# xx_backplane_shield_xi.net
KiCad netlist of a schematic drawn in EAGLE
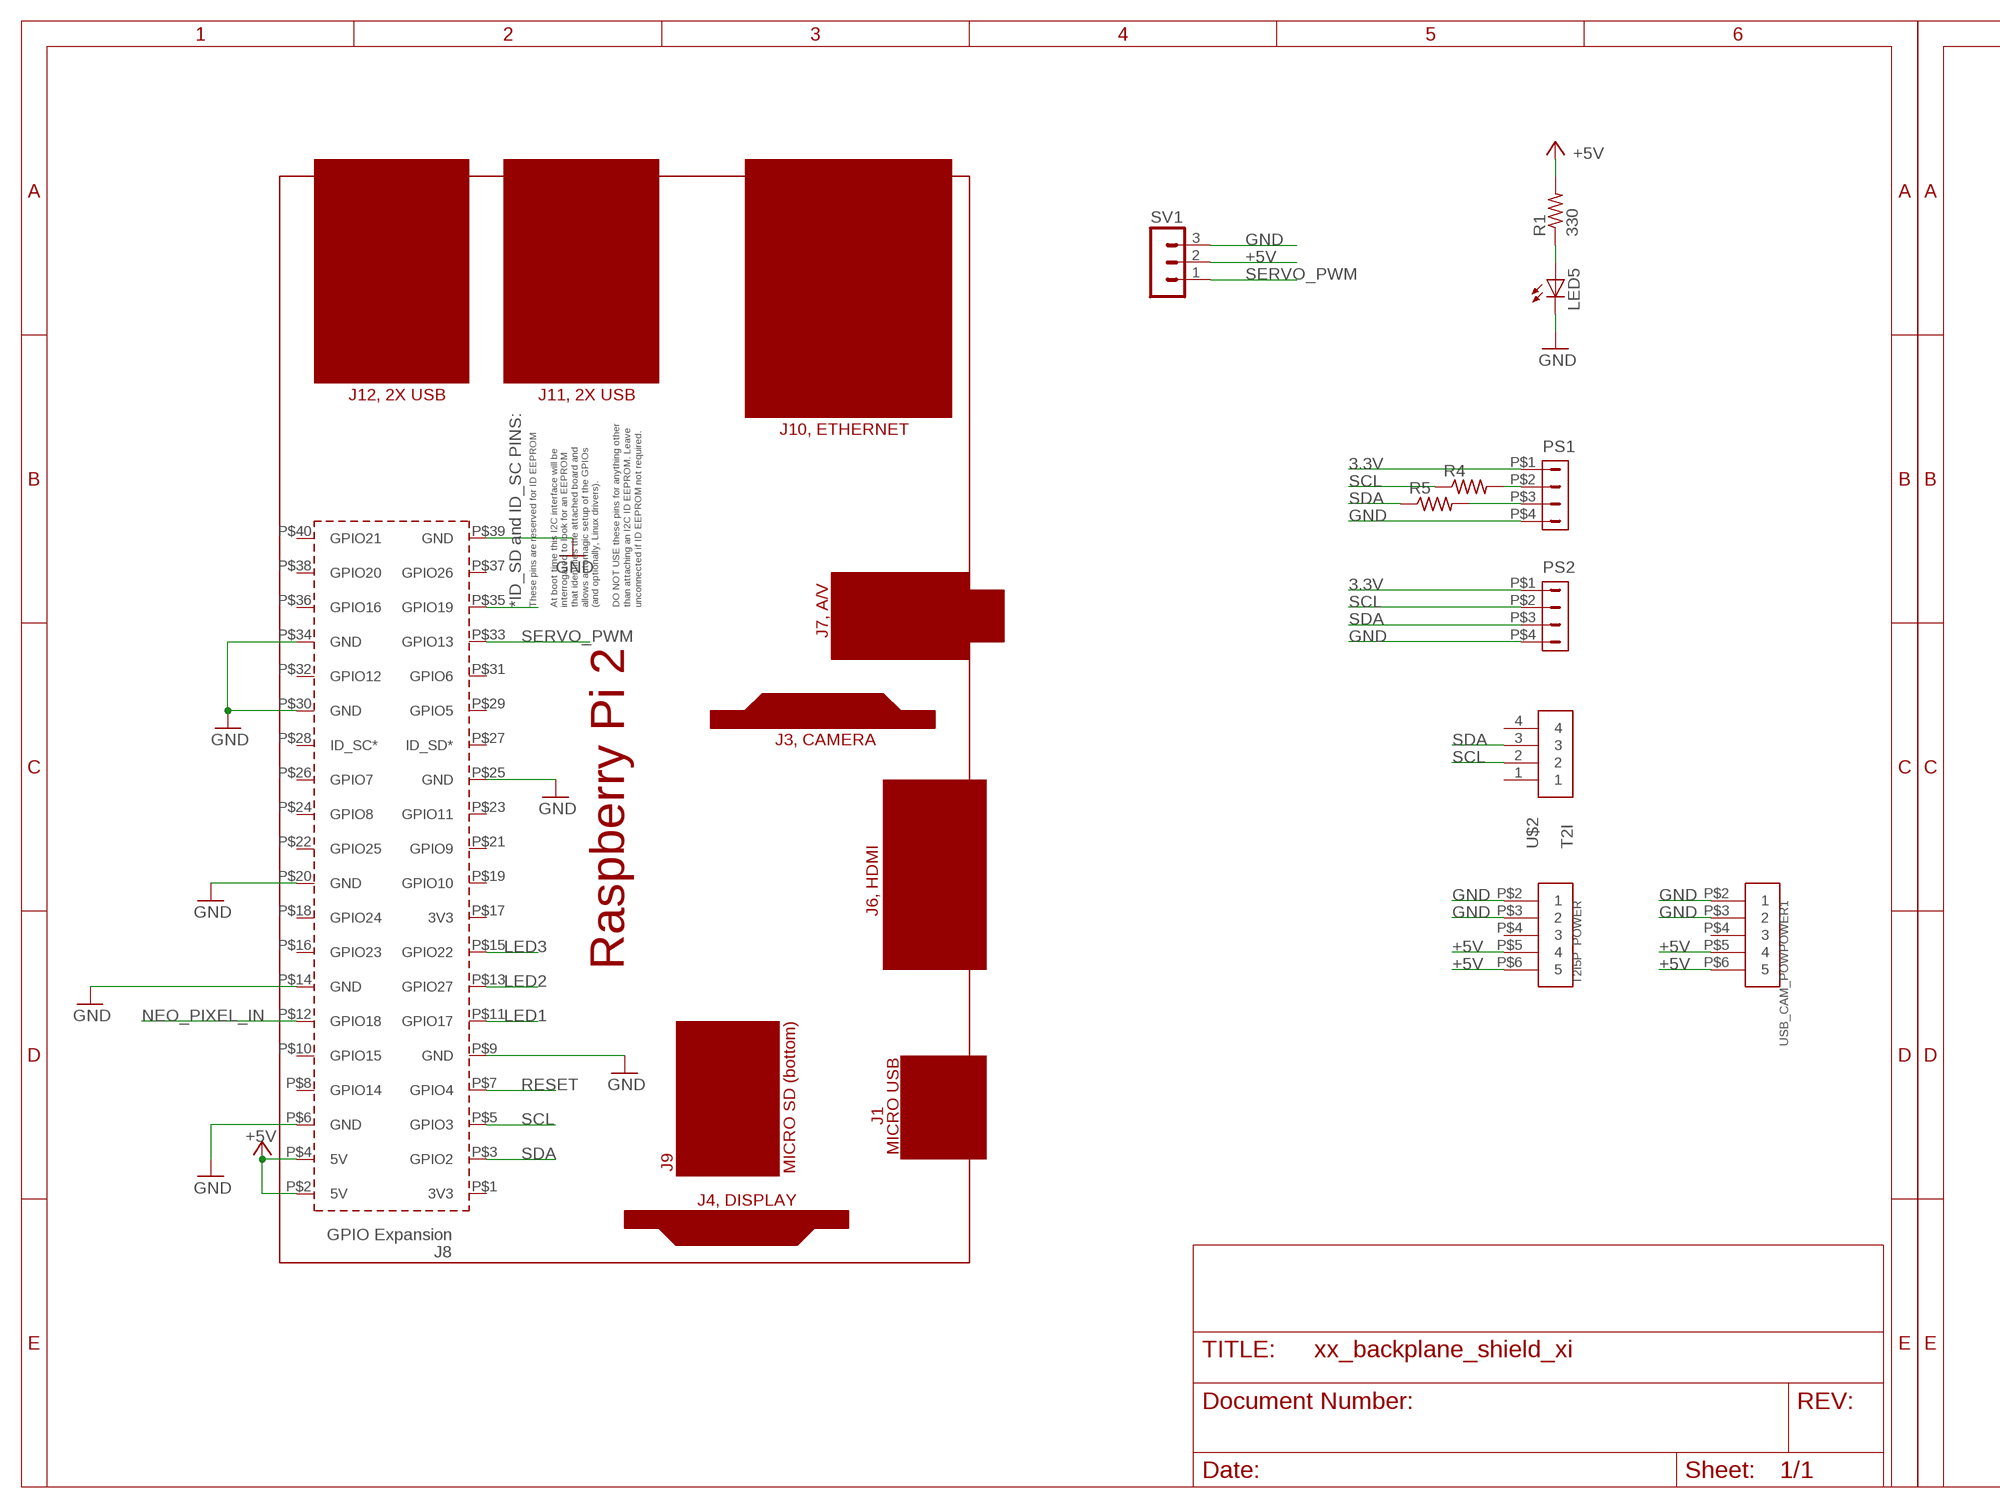
[diagram p0: schematic, sheet 1, part 1 of 2]
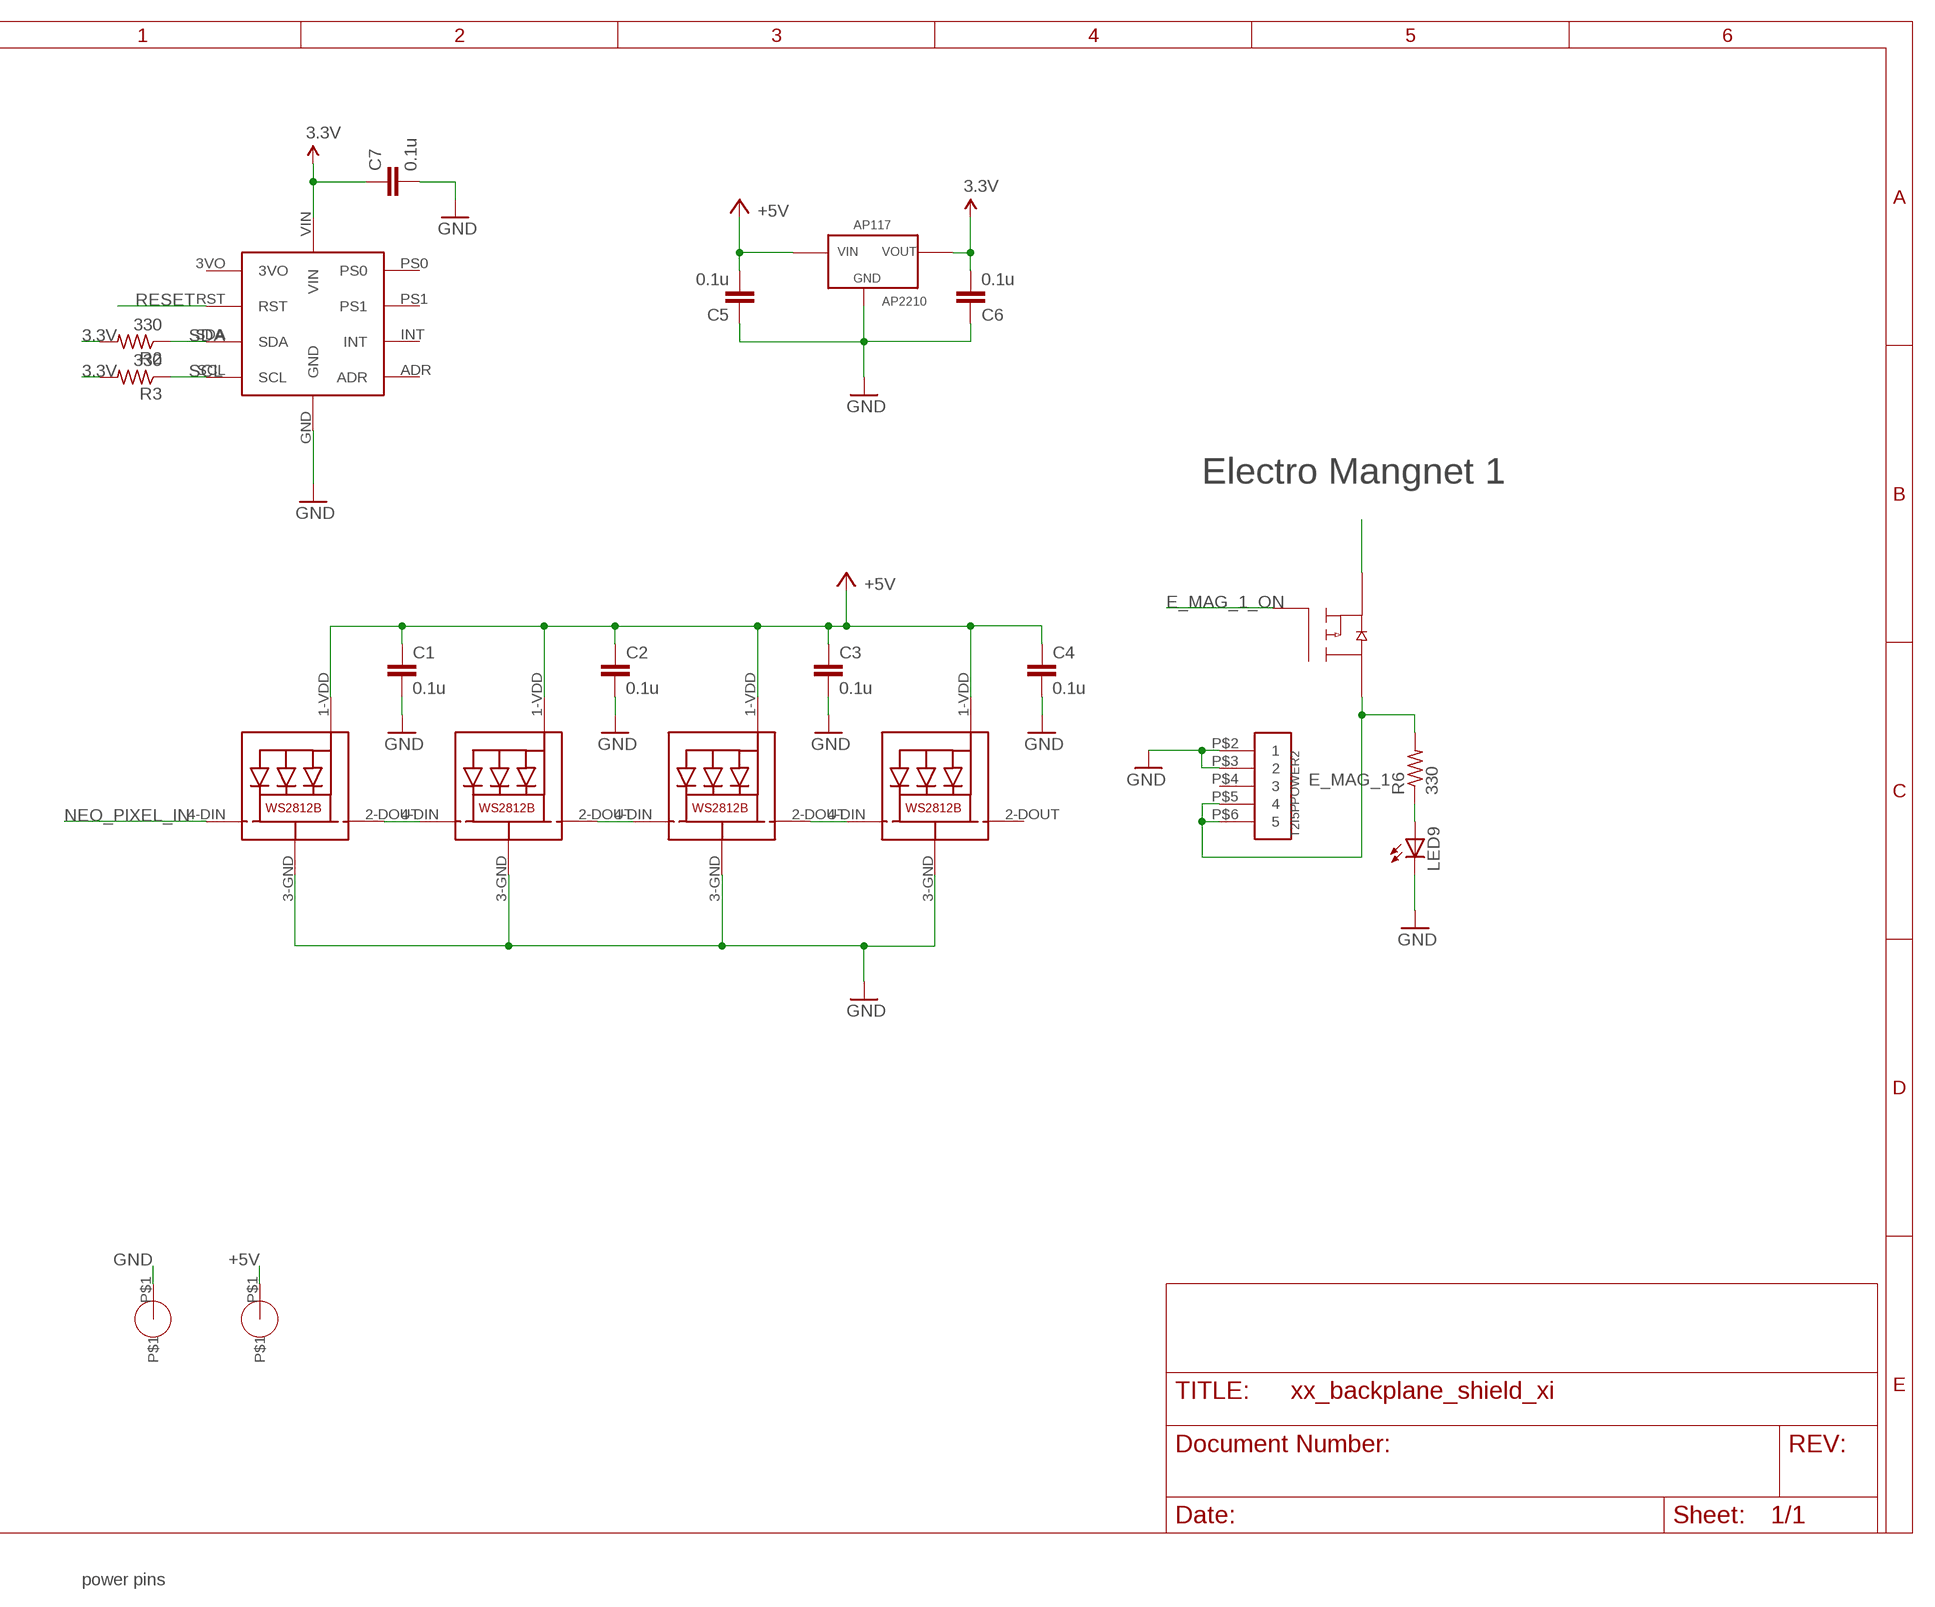
[diagram p1: schematic, sheet 1, part 2 of 2]

(export (version "E")
  (design (tool "Eeschema 10.0.6"))
  (components
    (comp (ref "C1")
      (value "0.1u")
      (footprint "eagle-import:0603-CAP")
      (libsource (lib "eagle-import") (part "CAP0603-CAP"))
    )
    (comp (ref "C2")
      (value "0.1u")
      (footprint "eagle-import:0603-CAP")
      (libsource (lib "eagle-import") (part "CAP0603-CAP"))
    )
    (comp (ref "C3")
      (value "0.1u")
      (footprint "eagle-import:0603-CAP")
      (libsource (lib "eagle-import") (part "CAP0603-CAP"))
    )
    (comp (ref "C4")
      (value "0.1u")
      (footprint "eagle-import:0603-CAP")
      (libsource (lib "eagle-import") (part "CAP0603-CAP"))
    )
    (comp (ref "C5")
      (value "0.1u")
      (footprint "eagle-import:0603-CAP")
      (libsource (lib "eagle-import") (part "CAP0603-CAP"))
    )
    (comp (ref "C6")
      (value "0.1u")
      (footprint "eagle-import:0603-CAP")
      (libsource (lib "eagle-import") (part "CAP0603-CAP"))
    )
    (comp (ref "C7")
      (value "0.1u")
      (footprint "eagle-import:0603-CAP")
      (libsource (lib "eagle-import") (part "CAP0603-CAP"))
    )
    (comp (ref "LED1")
      (value "WS2812B5050")
      (footprint "eagle-import:WS2812B")
      (libsource (lib "eagle-import") (part "WS2812B5050"))
    )
    (comp (ref "LED2")
      (value "WS2812B5050")
      (footprint "eagle-import:WS2812B")
      (libsource (lib "eagle-import") (part "WS2812B5050"))
    )
    (comp (ref "LED3")
      (value "WS2812B5050")
      (footprint "eagle-import:WS2812B")
      (libsource (lib "eagle-import") (part "WS2812B5050"))
    )
    (comp (ref "LED4")
      (value "WS2812B5050")
      (footprint "eagle-import:WS2812B")
      (libsource (lib "eagle-import") (part "WS2812B5050"))
    )
    (comp (ref "LED5")
      (value "LEDSML0603")
      (footprint "eagle-import:SML0603")
      (libsource (lib "eagle-import") (part "LEDSML0603"))
    )
    (comp (ref "LED9")
      (value "LEDSML0603")
      (footprint "eagle-import:SML0603")
      (libsource (lib "eagle-import") (part "LEDSML0603"))
    )
    (comp (ref "PCB1")
      (value "RPI2")
      (footprint "eagle-import:RPI2")
      (libsource (lib "eagle-import") (part "RPI2"))
    )
    (comp (ref "POWER")
      (value "T2I5P")
      (footprint "eagle-import:T2I5P")
      (libsource (lib "eagle-import") (part "T2I5P"))
    )
    (comp (ref "POWER1")
      (value "USB_CAM_POW")
      (footprint "eagle-import:T2I5P")
      (libsource (lib "eagle-import") (part "T2I5P"))
    )
    (comp (ref "POWER2")
      (value "T2I5P")
      (footprint "eagle-import:T2I5P")
      (libsource (lib "eagle-import") (part "T2I5P"))
    )
    (comp (ref "PS1")
      (value "DF13-4P-1.25DSA")
      (footprint "eagle-import:DF13-4P-1.25DSA")
      (libsource (lib "eagle-import") (part "DF13-4P-1.25DSA"))
    )
    (comp (ref "PS2")
      (value "DF13-4P-1.25DSA")
      (footprint "eagle-import:DF13-4P-1.25DSA")
      (libsource (lib "eagle-import") (part "DF13-4P-1.25DSA"))
    )
    (comp (ref "R1")
      (value "330")
      (footprint "eagle-import:R0603")
      (libsource (lib "eagle-import") (part "R-US_R0603"))
    )
    (comp (ref "R2")
      (value "330")
      (footprint "eagle-import:R0603")
      (libsource (lib "eagle-import") (part "R-US_R0603"))
    )
    (comp (ref "R3")
      (value "330")
      (footprint "eagle-import:R0603")
      (libsource (lib "eagle-import") (part "R-US_R0603"))
    )
    (comp (ref "R4")
      (value "0 Ohms")
      (footprint "eagle-import:R0603")
      (libsource (lib "eagle-import") (part "resistor_348_R-US_R0603"))
    )
    (comp (ref "R5")
      (value "0 ohms")
      (footprint "eagle-import:R0603")
      (libsource (lib "eagle-import") (part "resistor_348_R-US_R0603"))
    )
    (comp (ref "R6")
      (value "330")
      (footprint "eagle-import:R0603")
      (libsource (lib "eagle-import") (part "R-US_R0603"))
    )
    (comp (ref "SV1")
      (value "MA03-1")
      (footprint "eagle-import:MA03-1")
      (libsource (lib "eagle-import") (part "MA03-1"))
    )
    (comp (ref "U$2")
      (value "T2I")
      (footprint "eagle-import:T2I")
      (libsource (lib "eagle-import") (part "T2I"))
    )
    (comp (ref "U$3")
      (value "BNO055_9DOF_BREAKOUT")
      (footprint "eagle-import:BNO055")
      (libsource (lib "eagle-import") (part "BNO055_9DOF_BREAKOUT"))
    )
    (comp (ref "U$4")
      (value "THROUGHOLE")
      (footprint "eagle-import:THROUGHHOLE")
      (libsource (lib "eagle-import") (part "THROUGHOLE"))
    )
    (comp (ref "U$5")
      (value "AP2210")
      (footprint "eagle-import:SOT-23-3")
      (libsource (lib "eagle-import") (part "AP2210"))
    )
    (comp (ref "U$6")
      (value "THROUGHOLE")
      (footprint "eagle-import:THROUGHHOLE")
      (libsource (lib "eagle-import") (part "THROUGHOLE"))
    )
    (comp (ref "U1")
      (value "FQB27P06")
      (footprint "eagle-import:TO263-3")
      (libsource (lib "eagle-import") (part "FQB27P06"))
    )
  )
  (nets
    (net (code "1") (name "+5V") (class "Default")
      (node (ref "C1") (pin "1") (pinfunction "1_1") (pintype "passive"))
      (node (ref "C2") (pin "1") (pinfunction "1_1") (pintype "passive"))
      (node (ref "C3") (pin "1") (pinfunction "1_1") (pintype "passive"))
      (node (ref "C4") (pin "1") (pinfunction "1_1") (pintype "passive"))
      (node (ref "C5") (pin "2") (pinfunction "2_2") (pintype "passive"))
      (node (ref "LED1") (pin "1-VDD") (pinfunction "VDD_1-VDD") (pintype "power_in"))
      (node (ref "LED2") (pin "1-VDD") (pinfunction "VDD_1-VDD") (pintype "power_in"))
      (node (ref "LED3") (pin "1-VDD") (pinfunction "VDD_1-VDD") (pintype "power_in"))
      (node (ref "LED4") (pin "1-VDD") (pinfunction "VDD_1-VDD") (pintype "power_in"))
      (node (ref "PCB1") (pin "P$2") (pinfunction "5V_P$2") (pintype "bidirectional"))
      (node (ref "PCB1") (pin "P$4") (pinfunction "5V_P$4") (pintype "bidirectional"))
      (node (ref "POWER") (pin "P$5") (pinfunction "4_P$5") (pintype "bidirectional"))
      (node (ref "POWER") (pin "P$6") (pinfunction "5_P$6") (pintype "bidirectional"))
      (node (ref "POWER1") (pin "P$5") (pinfunction "4_P$5") (pintype "bidirectional"))
      (node (ref "POWER1") (pin "P$6") (pinfunction "5_P$6") (pintype "bidirectional"))
      (node (ref "R1") (pin "2") (pinfunction "2_2") (pintype "passive"))
      (node (ref "SV1") (pin "2") (pinfunction "2_2") (pintype "passive"))
      (node (ref "U$4") (pin "P$1") (pinfunction "P$1_P$1") (pintype "bidirectional"))
      (node (ref "U$5") (pin "VIN") (pinfunction "VIN_VIN") (pintype "input"))
      (node (ref "U1") (pin "3") (pinfunction "S2_3") (pintype "bidirectional"))
    )
    (net (code "2") (name "/E_MAG_1") (class "Default")
      (node (ref "POWER2") (pin "P$5") (pinfunction "4_P$5") (pintype "bidirectional"))
      (node (ref "POWER2") (pin "P$6") (pinfunction "5_P$6") (pintype "bidirectional"))
      (node (ref "R6") (pin "2") (pinfunction "2_2") (pintype "passive"))
      (node (ref "U1") (pin "TAB") (pinfunction "D2_TAB") (pintype "bidirectional"))
    )
    (net (code "3") (name "/E_MAG_1_ON") (class "Default")
      (node (ref "PCB1") (pin "P$35") (pinfunction "GPIO19_P$35") (pintype "bidirectional"))
      (node (ref "U1") (pin "1") (pinfunction "G2_1") (pintype "bidirectional"))
    )
    (net (code "4") (name "/LED1") (class "Default")
      (node (ref "PCB1") (pin "P$11") (pinfunction "GPIO17_P$11") (pintype "bidirectional"))
    )
    (net (code "5") (name "/LED2") (class "Default")
      (node (ref "PCB1") (pin "P$13") (pinfunction "GPIO27_P$13") (pintype "bidirectional"))
    )
    (net (code "6") (name "/LED3") (class "Default")
      (node (ref "PCB1") (pin "P$15") (pinfunction "GPIO22_P$15") (pintype "bidirectional"))
    )
    (net (code "7") (name "/NEO_PIXEL_IN") (class "Default")
      (node (ref "LED1") (pin "4-DIN") (pinfunction "DI_4-DIN") (pintype "input"))
      (node (ref "PCB1") (pin "P$12") (pinfunction "GPIO18_P$12") (pintype "bidirectional"))
    )
    (net (code "8") (name "/RESET") (class "Default")
      (node (ref "PCB1") (pin "P$7") (pinfunction "GPIO4_P$7") (pintype "bidirectional"))
      (node (ref "U$3") (pin "RST") (pinfunction "RST_RST") (pintype "bidirectional"))
    )
    (net (code "9") (name "/SCL") (class "Default")
      (node (ref "PCB1") (pin "P$5") (pinfunction "GPIO3_P$5") (pintype "bidirectional"))
      (node (ref "PS2") (pin "P$2") (pinfunction "2_P$2") (pintype "passive"))
      (node (ref "R3") (pin "1") (pinfunction "1_1") (pintype "passive"))
      (node (ref "R4") (pin "1") (pinfunction "1_1") (pintype "passive"))
      (node (ref "U$2") (pin "2") (pinfunction "2_2") (pintype "bidirectional"))
      (node (ref "U$3") (pin "SCL") (pinfunction "SCL_SCL") (pintype "bidirectional"))
    )
    (net (code "10") (name "/SDA") (class "Default")
      (node (ref "PCB1") (pin "P$3") (pinfunction "GPIO2_P$3") (pintype "bidirectional"))
      (node (ref "PS2") (pin "P$3") (pinfunction "3_P$3") (pintype "passive"))
      (node (ref "R2") (pin "1") (pinfunction "1_1") (pintype "passive"))
      (node (ref "R5") (pin "1") (pinfunction "1_1") (pintype "passive"))
      (node (ref "U$2") (pin "3") (pinfunction "3_3") (pintype "bidirectional"))
      (node (ref "U$3") (pin "SDA") (pinfunction "SDA_SDA") (pintype "bidirectional"))
    )
    (net (code "11") (name "/SERVO_PWM") (class "Default")
      (node (ref "PCB1") (pin "P$33") (pinfunction "GPIO13_P$33") (pintype "bidirectional"))
      (node (ref "SV1") (pin "1") (pinfunction "1_1") (pintype "passive"))
    )
    (net (code "12") (name "3.3V") (class "Default")
      (node (ref "C6") (pin "2") (pinfunction "2_2") (pintype "passive"))
      (node (ref "C7") (pin "1") (pinfunction "1_1") (pintype "passive"))
      (node (ref "PS1") (pin "P$1") (pinfunction "1_P$1") (pintype "passive"))
      (node (ref "PS2") (pin "P$1") (pinfunction "1_P$1") (pintype "passive"))
      (node (ref "R2") (pin "2") (pinfunction "2_2") (pintype "passive"))
      (node (ref "R3") (pin "2") (pinfunction "2_2") (pintype "passive"))
      (node (ref "U$3") (pin "VIN") (pinfunction "VIN_VIN") (pintype "bidirectional"))
      (node (ref "U$5") (pin "VOUT") (pinfunction "VOUT_VOUT") (pintype "output"))
    )
    (net (code "13") (name "GND") (class "Default")
      (node (ref "C1") (pin "2") (pinfunction "2_2") (pintype "passive"))
      (node (ref "C2") (pin "2") (pinfunction "2_2") (pintype "passive"))
      (node (ref "C3") (pin "2") (pinfunction "2_2") (pintype "passive"))
      (node (ref "C4") (pin "2") (pinfunction "2_2") (pintype "passive"))
      (node (ref "C5") (pin "1") (pinfunction "1_1") (pintype "passive"))
      (node (ref "C6") (pin "1") (pinfunction "1_1") (pintype "passive"))
      (node (ref "C7") (pin "2") (pinfunction "2_2") (pintype "passive"))
      (node (ref "LED1") (pin "3-GND") (pinfunction "GND_3-GND") (pintype "power_in"))
      (node (ref "LED2") (pin "3-GND") (pinfunction "GND_3-GND") (pintype "power_in"))
      (node (ref "LED3") (pin "3-GND") (pinfunction "GND_3-GND") (pintype "power_in"))
      (node (ref "LED4") (pin "3-GND") (pinfunction "GND_3-GND") (pintype "power_in"))
      (node (ref "LED5") (pin "C") (pinfunction "C_C") (pintype "passive"))
      (node (ref "LED9") (pin "C") (pinfunction "C_C") (pintype "passive"))
      (node (ref "PCB1") (pin "P$14") (pinfunction "GND_P$14") (pintype "bidirectional"))
      (node (ref "PCB1") (pin "P$20") (pinfunction "GND_P$20") (pintype "bidirectional"))
      (node (ref "PCB1") (pin "P$25") (pinfunction "GND_P$25") (pintype "bidirectional"))
      (node (ref "PCB1") (pin "P$30") (pinfunction "GND_P$30") (pintype "bidirectional"))
      (node (ref "PCB1") (pin "P$34") (pinfunction "GND_P$34") (pintype "bidirectional"))
      (node (ref "PCB1") (pin "P$39") (pinfunction "GND_P$39") (pintype "bidirectional"))
      (node (ref "PCB1") (pin "P$6") (pinfunction "GND_P$6") (pintype "bidirectional"))
      (node (ref "PCB1") (pin "P$9") (pinfunction "GND_P$9") (pintype "bidirectional"))
      (node (ref "POWER") (pin "P$2") (pinfunction "1_P$2") (pintype "bidirectional"))
      (node (ref "POWER") (pin "P$3") (pinfunction "2_P$3") (pintype "bidirectional"))
      (node (ref "POWER1") (pin "P$2") (pinfunction "1_P$2") (pintype "bidirectional"))
      (node (ref "POWER1") (pin "P$3") (pinfunction "2_P$3") (pintype "bidirectional"))
      (node (ref "POWER2") (pin "P$2") (pinfunction "1_P$2") (pintype "bidirectional"))
      (node (ref "POWER2") (pin "P$3") (pinfunction "2_P$3") (pintype "bidirectional"))
      (node (ref "PS1") (pin "P$4") (pinfunction "4_P$4") (pintype "passive"))
      (node (ref "PS2") (pin "P$4") (pinfunction "4_P$4") (pintype "passive"))
      (node (ref "SV1") (pin "3") (pinfunction "3_3") (pintype "passive"))
      (node (ref "U$3") (pin "GND") (pinfunction "GND_GND") (pintype "bidirectional"))
      (node (ref "U$5") (pin "GND") (pinfunction "GND_GND") (pintype "bidirectional"))
      (node (ref "U$6") (pin "P$1") (pinfunction "P$1_P$1") (pintype "bidirectional"))
    )
    (net (code "14") (name "Net-(LED1-DO)") (class "Default")
      (node (ref "LED1") (pin "2-DOUT") (pinfunction "DO_2-DOUT") (pintype "output"))
      (node (ref "LED2") (pin "4-DIN") (pinfunction "DI_4-DIN") (pintype "input"))
    )
    (net (code "15") (name "Net-(LED2-DO)") (class "Default")
      (node (ref "LED2") (pin "2-DOUT") (pinfunction "DO_2-DOUT") (pintype "output"))
      (node (ref "LED3") (pin "4-DIN") (pinfunction "DI_4-DIN") (pintype "input"))
    )
    (net (code "16") (name "Net-(LED3-DO)") (class "Default")
      (node (ref "LED3") (pin "2-DOUT") (pinfunction "DO_2-DOUT") (pintype "output"))
      (node (ref "LED4") (pin "4-DIN") (pinfunction "DI_4-DIN") (pintype "input"))
    )
    (net (code "17") (name "Net-(LED5-PadA)") (class "Default")
      (node (ref "LED5") (pin "A") (pinfunction "A_A") (pintype "passive"))
      (node (ref "R1") (pin "1") (pinfunction "1_1") (pintype "passive"))
    )
    (net (code "18") (name "Net-(LED9-PadA)") (class "Default")
      (node (ref "LED9") (pin "A") (pinfunction "A_A") (pintype "passive"))
      (node (ref "R6") (pin "1") (pinfunction "1_1") (pintype "passive"))
    )
    (net (code "19") (name "Net-(PS1-2)") (class "Default")
      (node (ref "PS1") (pin "P$2") (pinfunction "2_P$2") (pintype "passive"))
      (node (ref "R4") (pin "2") (pinfunction "2_2") (pintype "passive"))
    )
    (net (code "20") (name "Net-(PS1-3)") (class "Default")
      (node (ref "PS1") (pin "P$3") (pinfunction "3_P$3") (pintype "passive"))
      (node (ref "R5") (pin "2") (pinfunction "2_2") (pintype "passive"))
    )
    (net (code "21") (name "unconnected-(LED4-DO-Pad2-DOUT)") (class "Default")
      (node (ref "LED4") (pin "2-DOUT") (pinfunction "DO_2-DOUT") (pintype "output"))
    )
    (net (code "22") (name "unconnected-(PCB1-3V3-PadP$1)") (class "Default")
      (node (ref "PCB1") (pin "P$1") (pinfunction "3V3_P$1") (pintype "bidirectional"))
    )
    (net (code "23") (name "unconnected-(PCB1-3V3-PadP$17)") (class "Default")
      (node (ref "PCB1") (pin "P$17") (pinfunction "3V3_P$17") (pintype "bidirectional"))
    )
    (net (code "24") (name "unconnected-(PCB1-GPIO5-PadP$29)") (class "Default")
      (node (ref "PCB1") (pin "P$29") (pinfunction "GPIO5_P$29") (pintype "bidirectional"))
    )
    (net (code "25") (name "unconnected-(PCB1-GPIO6-PadP$31)") (class "Default")
      (node (ref "PCB1") (pin "P$31") (pinfunction "GPIO6_P$31") (pintype "bidirectional"))
    )
    (net (code "26") (name "unconnected-(PCB1-GPIO7-PadP$26)") (class "Default")
      (node (ref "PCB1") (pin "P$26") (pinfunction "GPIO7_P$26") (pintype "bidirectional"))
    )
    (net (code "27") (name "unconnected-(PCB1-GPIO8-PadP$24)") (class "Default")
      (node (ref "PCB1") (pin "P$24") (pinfunction "GPIO8_P$24") (pintype "bidirectional"))
    )
    (net (code "28") (name "unconnected-(PCB1-GPIO9-PadP$21)") (class "Default")
      (node (ref "PCB1") (pin "P$21") (pinfunction "GPIO9_P$21") (pintype "bidirectional"))
    )
    (net (code "29") (name "unconnected-(PCB1-GPIO10-PadP$19)") (class "Default")
      (node (ref "PCB1") (pin "P$19") (pinfunction "GPIO10_P$19") (pintype "bidirectional"))
    )
    (net (code "30") (name "unconnected-(PCB1-GPIO11-PadP$23)") (class "Default")
      (node (ref "PCB1") (pin "P$23") (pinfunction "GPIO11_P$23") (pintype "bidirectional"))
    )
    (net (code "31") (name "unconnected-(PCB1-GPIO12-PadP$32)") (class "Default")
      (node (ref "PCB1") (pin "P$32") (pinfunction "GPIO12_P$32") (pintype "bidirectional"))
    )
    (net (code "32") (name "unconnected-(PCB1-GPIO14-PadP$8)") (class "Default")
      (node (ref "PCB1") (pin "P$8") (pinfunction "GPIO14_P$8") (pintype "bidirectional"))
    )
    (net (code "33") (name "unconnected-(PCB1-GPIO15-PadP$10)") (class "Default")
      (node (ref "PCB1") (pin "P$10") (pinfunction "GPIO15_P$10") (pintype "bidirectional"))
    )
    (net (code "34") (name "unconnected-(PCB1-GPIO16-PadP$36)") (class "Default")
      (node (ref "PCB1") (pin "P$36") (pinfunction "GPIO16_P$36") (pintype "bidirectional"))
    )
    (net (code "35") (name "unconnected-(PCB1-GPIO20-PadP$38)") (class "Default")
      (node (ref "PCB1") (pin "P$38") (pinfunction "GPIO20_P$38") (pintype "bidirectional"))
    )
    (net (code "36") (name "unconnected-(PCB1-GPIO21-PadP$40)") (class "Default")
      (node (ref "PCB1") (pin "P$40") (pinfunction "GPIO21_P$40") (pintype "bidirectional"))
    )
    (net (code "37") (name "unconnected-(PCB1-GPIO23-PadP$16)") (class "Default")
      (node (ref "PCB1") (pin "P$16") (pinfunction "GPIO23_P$16") (pintype "bidirectional"))
    )
    (net (code "38") (name "unconnected-(PCB1-GPIO24-PadP$18)") (class "Default")
      (node (ref "PCB1") (pin "P$18") (pinfunction "GPIO24_P$18") (pintype "bidirectional"))
    )
    (net (code "39") (name "unconnected-(PCB1-GPIO25-PadP$22)") (class "Default")
      (node (ref "PCB1") (pin "P$22") (pinfunction "GPIO25_P$22") (pintype "bidirectional"))
    )
    (net (code "40") (name "unconnected-(PCB1-GPIO26-PadP$37)") (class "Default")
      (node (ref "PCB1") (pin "P$37") (pinfunction "GPIO26_P$37") (pintype "bidirectional"))
    )
    (net (code "41") (name "unconnected-(PCB1-ID_SC*-PadP$28)") (class "Default")
      (node (ref "PCB1") (pin "P$28") (pinfunction "ID_SC*_P$28") (pintype "bidirectional"))
    )
    (net (code "42") (name "unconnected-(PCB1-ID_SD*-PadP$27)") (class "Default")
      (node (ref "PCB1") (pin "P$27") (pinfunction "ID_SD*_P$27") (pintype "bidirectional"))
    )
    (net (code "43") (name "unconnected-(POWER-3-PadP$4)") (class "Default")
      (node (ref "POWER") (pin "P$4") (pinfunction "3_P$4") (pintype "bidirectional"))
    )
    (net (code "44") (name "unconnected-(POWER1-3-PadP$4)") (class "Default")
      (node (ref "POWER1") (pin "P$4") (pinfunction "3_P$4") (pintype "bidirectional"))
    )
    (net (code "45") (name "unconnected-(POWER2-3-PadP$4)") (class "Default")
      (node (ref "POWER2") (pin "P$4") (pinfunction "3_P$4") (pintype "bidirectional"))
    )
    (net (code "46") (name "unconnected-(U$2-Pad1)") (class "Default")
      (node (ref "U$2") (pin "1") (pinfunction "1_1") (pintype "bidirectional"))
    )
    (net (code "47") (name "unconnected-(U$2-Pad4)") (class "Default")
      (node (ref "U$2") (pin "4") (pinfunction "4_4") (pintype "bidirectional"))
    )
    (net (code "48") (name "unconnected-(U$3-Pad3VO)") (class "Default")
      (node (ref "U$3") (pin "3VO") (pinfunction "3VO_3VO") (pintype "bidirectional"))
    )
    (net (code "49") (name "unconnected-(U$3-PadADR)") (class "Default")
      (node (ref "U$3") (pin "ADR") (pinfunction "ADR_ADR") (pintype "bidirectional"))
    )
    (net (code "50") (name "unconnected-(U$3-PadINT)") (class "Default")
      (node (ref "U$3") (pin "INT") (pinfunction "INT_INT") (pintype "bidirectional"))
    )
    (net (code "51") (name "unconnected-(U$3-PadPS0)") (class "Default")
      (node (ref "U$3") (pin "PS0") (pinfunction "PS0_PS0") (pintype "bidirectional"))
    )
    (net (code "52") (name "unconnected-(U$3-PadPS1)") (class "Default")
      (node (ref "U$3") (pin "PS1") (pinfunction "PS1_PS1") (pintype "bidirectional"))
    )
  )
)
